# BLDC_Motor_Driver.net
KiCad netlist of a schematic drawn in EAGLE
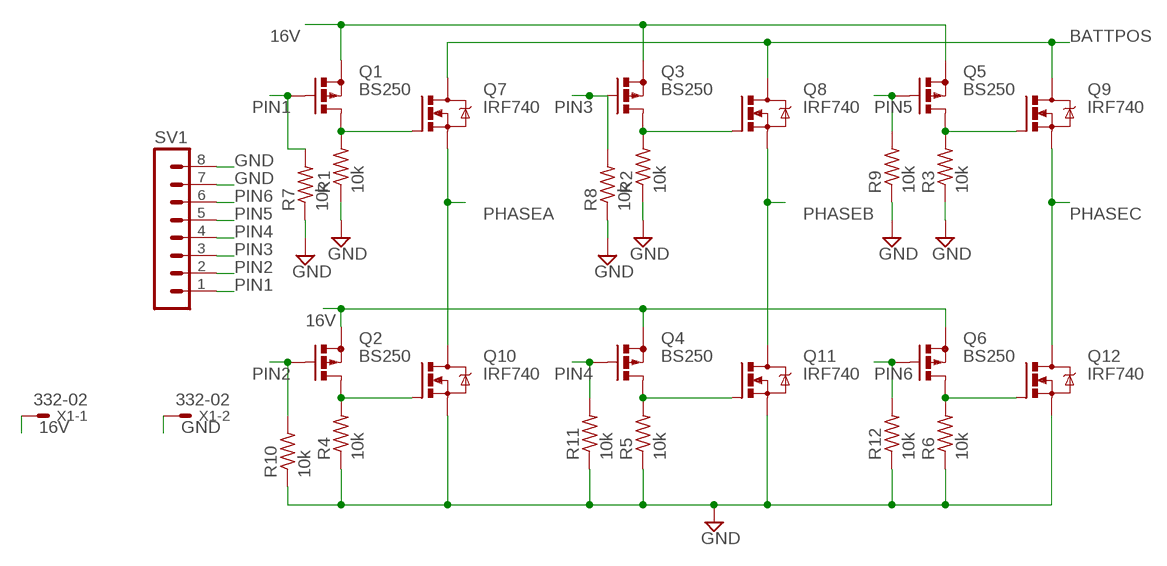
[diagram p0: schematic, sheet 1]

(export (version "E")
  (design (tool "Eeschema 10.0.6"))
  (components
    (comp (ref "Q1")
      (value "BS250")
      (footprint "eagle-import:SOT54E")
      (libsource (lib "eagle-import") (part "BS250"))
    )
    (comp (ref "Q2")
      (value "BS250")
      (footprint "eagle-import:SOT54E")
      (libsource (lib "eagle-import") (part "BS250"))
    )
    (comp (ref "Q3")
      (value "BS250")
      (footprint "eagle-import:SOT54E")
      (libsource (lib "eagle-import") (part "BS250"))
    )
    (comp (ref "Q4")
      (value "BS250")
      (footprint "eagle-import:SOT54E")
      (libsource (lib "eagle-import") (part "BS250"))
    )
    (comp (ref "Q5")
      (value "BS250")
      (footprint "eagle-import:SOT54E")
      (libsource (lib "eagle-import") (part "BS250"))
    )
    (comp (ref "Q6")
      (value "BS250")
      (footprint "eagle-import:SOT54E")
      (libsource (lib "eagle-import") (part "BS250"))
    )
    (comp (ref "Q7")
      (value "IRF740")
      (footprint "eagle-import:TO220BV")
      (libsource (lib "eagle-import") (part "IRF740"))
    )
    (comp (ref "Q8")
      (value "IRF740")
      (footprint "eagle-import:TO220BV")
      (libsource (lib "eagle-import") (part "IRF740"))
    )
    (comp (ref "Q9")
      (value "IRF740")
      (footprint "eagle-import:TO220BV")
      (libsource (lib "eagle-import") (part "IRF740"))
    )
    (comp (ref "Q10")
      (value "IRF740")
      (footprint "eagle-import:TO220BV")
      (libsource (lib "eagle-import") (part "IRF740"))
    )
    (comp (ref "Q11")
      (value "IRF740")
      (footprint "eagle-import:TO220BV")
      (libsource (lib "eagle-import") (part "IRF740"))
    )
    (comp (ref "Q12")
      (value "IRF740")
      (footprint "eagle-import:TO220BV")
      (libsource (lib "eagle-import") (part "IRF740"))
    )
    (comp (ref "R1")
      (value "10k")
      (footprint "eagle-import:R0805")
      (libsource (lib "eagle-import") (part "R-US_R0805"))
    )
    (comp (ref "R2")
      (value "10k")
      (footprint "eagle-import:R0805")
      (libsource (lib "eagle-import") (part "R-US_R0805"))
    )
    (comp (ref "R3")
      (value "10k")
      (footprint "eagle-import:R0805")
      (libsource (lib "eagle-import") (part "R-US_R0805"))
    )
    (comp (ref "R4")
      (value "10k")
      (footprint "eagle-import:R0805")
      (libsource (lib "eagle-import") (part "R-US_R0805"))
    )
    (comp (ref "R5")
      (value "10k")
      (footprint "eagle-import:R0805")
      (libsource (lib "eagle-import") (part "R-US_R0805"))
    )
    (comp (ref "R6")
      (value "10k")
      (footprint "eagle-import:R0805")
      (libsource (lib "eagle-import") (part "R-US_R0805"))
    )
    (comp (ref "R7")
      (value "10k")
      (footprint "eagle-import:R0805")
      (libsource (lib "eagle-import") (part "R-US_R0805"))
    )
    (comp (ref "R8")
      (value "10k")
      (footprint "eagle-import:R0805")
      (libsource (lib "eagle-import") (part "R-US_R0805"))
    )
    (comp (ref "R9")
      (value "10k")
      (footprint "eagle-import:R0805")
      (libsource (lib "eagle-import") (part "R-US_R0805"))
    )
    (comp (ref "R10")
      (value "10k")
      (footprint "eagle-import:R0805")
      (libsource (lib "eagle-import") (part "R-US_R0805"))
    )
    (comp (ref "R11")
      (value "10k")
      (footprint "eagle-import:R0805")
      (libsource (lib "eagle-import") (part "R-US_R0805"))
    )
    (comp (ref "R12")
      (value "10k")
      (footprint "eagle-import:R0805")
      (libsource (lib "eagle-import") (part "R-US_R0805"))
    )
    (comp (ref "SV1")
      (value "MA08-1")
      (footprint "eagle-import:MA08-1")
      (libsource (lib "eagle-import") (part "MA08-1"))
    )
    (comp (ref "X1")
      (value "332-02")
      (footprint "eagle-import:332-02")
      (libsource (lib "eagle-import") (part "332-02"))
    )
  )
  (nets
    (net (code "1") (name "/16V") (class "Default")
      (node (ref "Q1") (pin "S") (pinfunction "S_S") (pintype "passive"))
      (node (ref "Q2") (pin "S") (pinfunction "S_S") (pintype "passive"))
      (node (ref "Q3") (pin "S") (pinfunction "S_S") (pintype "passive"))
      (node (ref "Q4") (pin "S") (pinfunction "S_S") (pintype "passive"))
      (node (ref "Q5") (pin "S") (pinfunction "S_S") (pintype "passive"))
      (node (ref "Q6") (pin "S") (pinfunction "S_S") (pintype "passive"))
      (node (ref "X1") (pin "1") (pinfunction "S_1") (pintype "passive"))
    )
    (net (code "2") (name "/BATTPOS") (class "Default")
      (node (ref "Q7") (pin "D") (pinfunction "D_D") (pintype "passive"))
      (node (ref "Q8") (pin "D") (pinfunction "D_D") (pintype "passive"))
      (node (ref "Q9") (pin "D") (pinfunction "D_D") (pintype "passive"))
    )
    (net (code "3") (name "/PHASEA") (class "Default")
      (node (ref "Q10") (pin "D") (pinfunction "D_D") (pintype "passive"))
      (node (ref "Q7") (pin "S") (pinfunction "S_S") (pintype "passive"))
    )
    (net (code "4") (name "/PHASEB") (class "Default")
      (node (ref "Q11") (pin "D") (pinfunction "D_D") (pintype "passive"))
      (node (ref "Q8") (pin "S") (pinfunction "S_S") (pintype "passive"))
    )
    (net (code "5") (name "/PHASEC") (class "Default")
      (node (ref "Q12") (pin "D") (pinfunction "D_D") (pintype "passive"))
      (node (ref "Q9") (pin "S") (pinfunction "S_S") (pintype "passive"))
    )
    (net (code "6") (name "/PIN1") (class "Default")
      (node (ref "Q1") (pin "G") (pinfunction "G_G") (pintype "passive"))
      (node (ref "R7") (pin "2") (pinfunction "2_2") (pintype "passive"))
      (node (ref "SV1") (pin "1") (pinfunction "1_1") (pintype "passive"))
    )
    (net (code "7") (name "/PIN2") (class "Default")
      (node (ref "Q2") (pin "G") (pinfunction "G_G") (pintype "passive"))
      (node (ref "R10") (pin "2") (pinfunction "2_2") (pintype "passive"))
      (node (ref "SV1") (pin "2") (pinfunction "2_2") (pintype "passive"))
    )
    (net (code "8") (name "/PIN3") (class "Default")
      (node (ref "Q3") (pin "G") (pinfunction "G_G") (pintype "passive"))
      (node (ref "R8") (pin "2") (pinfunction "2_2") (pintype "passive"))
      (node (ref "SV1") (pin "3") (pinfunction "3_3") (pintype "passive"))
    )
    (net (code "9") (name "/PIN4") (class "Default")
      (node (ref "Q4") (pin "G") (pinfunction "G_G") (pintype "passive"))
      (node (ref "R11") (pin "2") (pinfunction "2_2") (pintype "passive"))
      (node (ref "SV1") (pin "4") (pinfunction "4_4") (pintype "passive"))
    )
    (net (code "10") (name "/PIN5") (class "Default")
      (node (ref "Q5") (pin "G") (pinfunction "G_G") (pintype "passive"))
      (node (ref "R9") (pin "2") (pinfunction "2_2") (pintype "passive"))
      (node (ref "SV1") (pin "5") (pinfunction "5_5") (pintype "passive"))
    )
    (net (code "11") (name "/PIN6") (class "Default")
      (node (ref "Q6") (pin "G") (pinfunction "G_G") (pintype "passive"))
      (node (ref "R12") (pin "2") (pinfunction "2_2") (pintype "passive"))
      (node (ref "SV1") (pin "6") (pinfunction "6_6") (pintype "passive"))
    )
    (net (code "12") (name "GND") (class "Default")
      (node (ref "Q10") (pin "S") (pinfunction "S_S") (pintype "passive"))
      (node (ref "Q11") (pin "S") (pinfunction "S_S") (pintype "passive"))
      (node (ref "Q12") (pin "S") (pinfunction "S_S") (pintype "passive"))
      (node (ref "R1") (pin "1") (pinfunction "1_1") (pintype "passive"))
      (node (ref "R10") (pin "1") (pinfunction "1_1") (pintype "passive"))
      (node (ref "R11") (pin "1") (pinfunction "1_1") (pintype "passive"))
      (node (ref "R12") (pin "1") (pinfunction "1_1") (pintype "passive"))
      (node (ref "R2") (pin "1") (pinfunction "1_1") (pintype "passive"))
      (node (ref "R3") (pin "1") (pinfunction "1_1") (pintype "passive"))
      (node (ref "R4") (pin "1") (pinfunction "1_1") (pintype "passive"))
      (node (ref "R5") (pin "1") (pinfunction "1_1") (pintype "passive"))
      (node (ref "R6") (pin "1") (pinfunction "1_1") (pintype "passive"))
      (node (ref "R7") (pin "1") (pinfunction "1_1") (pintype "passive"))
      (node (ref "R8") (pin "1") (pinfunction "1_1") (pintype "passive"))
      (node (ref "R9") (pin "1") (pinfunction "1_1") (pintype "passive"))
      (node (ref "SV1") (pin "7") (pinfunction "7_7") (pintype "passive"))
      (node (ref "SV1") (pin "8") (pinfunction "8_8") (pintype "passive"))
      (node (ref "X1") (pin "2") (pinfunction "S_2") (pintype "passive"))
    )
    (net (code "13") (name "Net-(Q1-PadD)") (class "Default")
      (node (ref "Q1") (pin "D") (pinfunction "D_D") (pintype "passive"))
      (node (ref "Q7") (pin "G") (pinfunction "G_G") (pintype "passive"))
      (node (ref "R1") (pin "2") (pinfunction "2_2") (pintype "passive"))
    )
    (net (code "14") (name "Net-(Q3-PadD)") (class "Default")
      (node (ref "Q3") (pin "D") (pinfunction "D_D") (pintype "passive"))
      (node (ref "Q8") (pin "G") (pinfunction "G_G") (pintype "passive"))
      (node (ref "R2") (pin "2") (pinfunction "2_2") (pintype "passive"))
    )
    (net (code "15") (name "Net-(Q5-PadD)") (class "Default")
      (node (ref "Q5") (pin "D") (pinfunction "D_D") (pintype "passive"))
      (node (ref "Q9") (pin "G") (pinfunction "G_G") (pintype "passive"))
      (node (ref "R3") (pin "2") (pinfunction "2_2") (pintype "passive"))
    )
    (net (code "16") (name "Net-(Q10-PadG)") (class "Default")
      (node (ref "Q10") (pin "G") (pinfunction "G_G") (pintype "passive"))
      (node (ref "Q2") (pin "D") (pinfunction "D_D") (pintype "passive"))
      (node (ref "R4") (pin "2") (pinfunction "2_2") (pintype "passive"))
    )
    (net (code "17") (name "Net-(Q11-PadG)") (class "Default")
      (node (ref "Q11") (pin "G") (pinfunction "G_G") (pintype "passive"))
      (node (ref "Q4") (pin "D") (pinfunction "D_D") (pintype "passive"))
      (node (ref "R5") (pin "2") (pinfunction "2_2") (pintype "passive"))
    )
    (net (code "18") (name "Net-(Q12-PadG)") (class "Default")
      (node (ref "Q12") (pin "G") (pinfunction "G_G") (pintype "passive"))
      (node (ref "Q6") (pin "D") (pinfunction "D_D") (pintype "passive"))
      (node (ref "R6") (pin "2") (pinfunction "2_2") (pintype "passive"))
    )
  )
)
